# OnOnfre_DevBoard_rev4.net
KiCad netlist of a schematic drawn in EAGLE
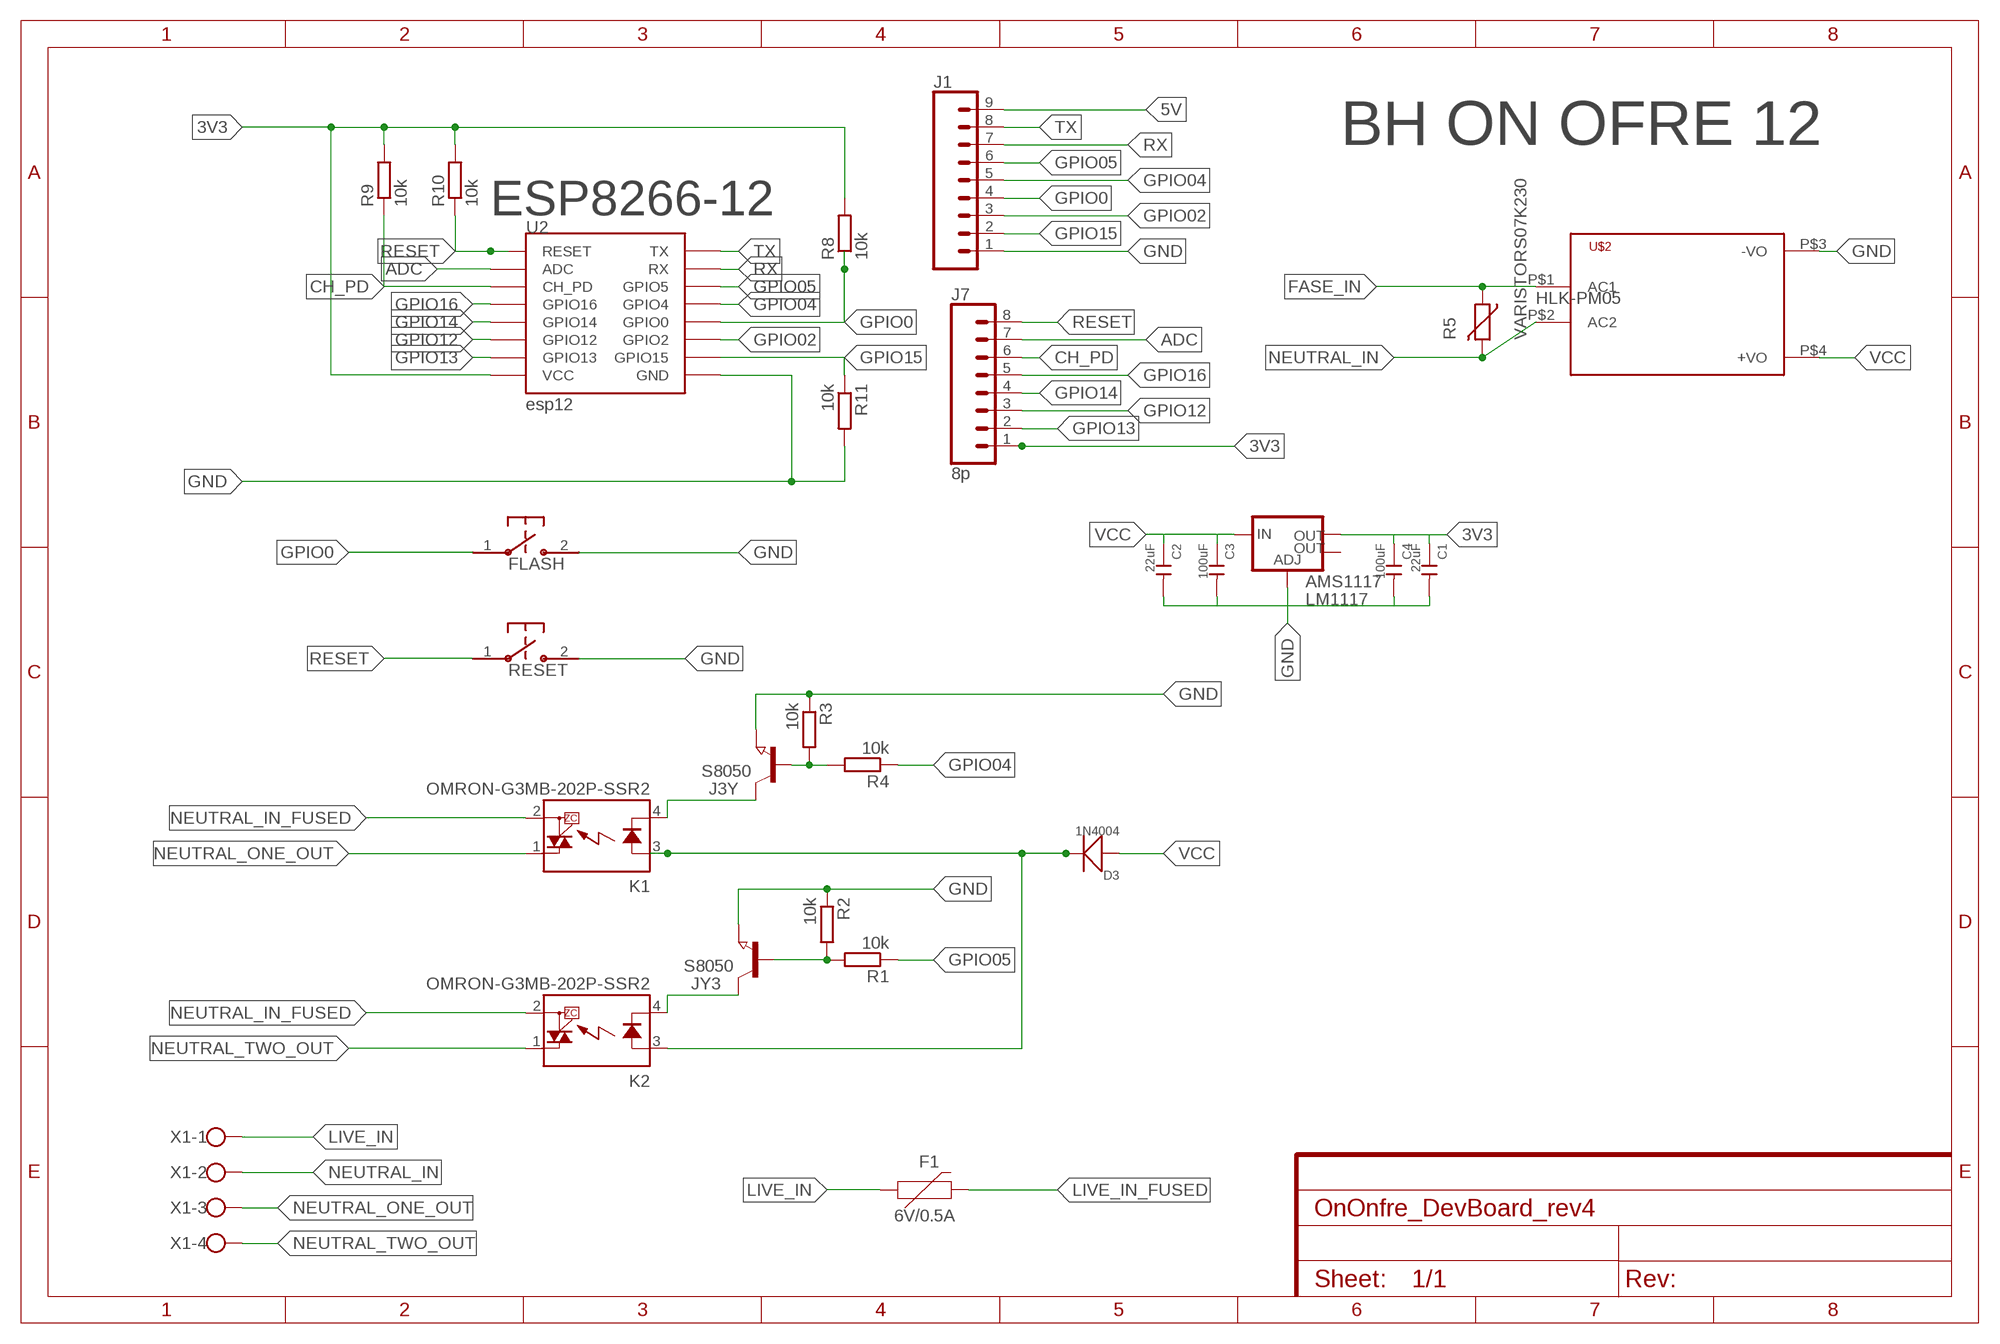
[diagram p0: schematic, sheet 1]

(export (version "E")
  (design (tool "Eeschema 10.0.6"))
  (components
    (comp (ref "AMS1117")
      (value "LM1117")
      (footprint "eagle-import:SOT223")
      (libsource (lib "eagle-import") (part "V_REG_LM1117SOT223"))
    )
    (comp (ref "C1")
      (value "22uF")
      (footprint "eagle-import:C1206")
      (fields (field (name "MPN") "CC1206KKX7RCBB102"))
      (libsource (lib "eagle-import") (part "CERAMIC-1NF-1KV-10%-X7R?(1206)"))
    )
    (comp (ref "C2")
      (value "22uF")
      (footprint "eagle-import:C1206")
      (fields (field (name "MPN") "CC1206KKX7RCBB102"))
      (libsource (lib "eagle-import") (part "CERAMIC-1NF-1KV-10%-X7R?(1206)"))
    )
    (comp (ref "C3")
      (value "100uF")
      (footprint "eagle-import:C1206")
      (fields (field (name "MPN") "CC1206KKX7RCBB102"))
      (libsource (lib "eagle-import") (part "CERAMIC-1NF-1KV-10%-X7R?(1206)"))
    )
    (comp (ref "C4")
      (value "100uF")
      (footprint "eagle-import:C1206")
      (fields (field (name "MPN") "CC1206KKX7RCBB102"))
      (libsource (lib "eagle-import") (part "CERAMIC-1NF-1KV-10%-X7R?(1206)"))
    )
    (comp (ref "D3")
      (value "1N4004")
      (footprint "eagle-import:DO-214AC")
      (fields (field (name "MPN") "1N4007"))
      (libsource (lib "eagle-import") (part "DIODE-GEN-PURPOSE-1KV-1A(DO-214AC)"))
    )
    (comp (ref "F1")
      (value "6V/0.5A")
      (footprint "eagle-import:1206")
      (libsource (lib "eagle-import") (part "PPTC_HALF-AMP"))
    )
    (comp (ref "FLASH")
      (value "B3U-1000P-2P-SMD")
      (footprint "eagle-import:B3U-1000P")
      (fields (field (name "MANUFACTURER") "Omron") (field (name "MPN") "B3U-1000P"))
      (libsource (lib "eagle-import") (part "B3U-1000P"))
    )
    (comp (ref "J1")
      (value "CONN_09")
      (footprint "eagle-import:1X09")
      (libsource (lib "eagle-import") (part "CONN_09"))
    )
    (comp (ref "J3Y")
      (value "S8050")
      (footprint "eagle-import:SOT23")
      (libsource (lib "eagle-import") (part "NPN-TRANSISTOR_SOT23"))
    )
    (comp (ref "J7")
      (value "8p")
      (footprint "eagle-import:1X08")
      (libsource (lib "eagle-import") (part "CONN_08{dblquote}"))
    )
    (comp (ref "JY3")
      (value "S8050")
      (footprint "eagle-import:SOT23")
      (libsource (lib "eagle-import") (part "NPN-TRANSISTOR_SOT23"))
    )
    (comp (ref "K1")
      (value "OMRON-G3MB-202P-SSR2")
      (footprint "eagle-import:OMRON-G3MB-202P-SSR")
      (fields (field (name "MPN") "S202S02F"))
      (libsource (lib "eagle-import") (part "OMRON-G3MB-202P-SSR2"))
    )
    (comp (ref "K2")
      (value "OMRON-G3MB-202P-SSR2")
      (footprint "eagle-import:OMRON-G3MB-202P-SSR")
      (fields (field (name "MPN") "S202S02F"))
      (libsource (lib "eagle-import") (part "OMRON-G3MB-202P-SSR2"))
    )
    (comp (ref "R1")
      (value "10k")
      (footprint "eagle-import:R0603")
      (libsource (lib "eagle-import") (part "R-EU_R0603"))
    )
    (comp (ref "R2")
      (value "10k")
      (footprint "eagle-import:R0603")
      (libsource (lib "eagle-import") (part "R-EU_R0603"))
    )
    (comp (ref "R3")
      (value "10k")
      (footprint "eagle-import:R0603")
      (libsource (lib "eagle-import") (part "R-EU_R0603"))
    )
    (comp (ref "R4")
      (value "10k")
      (footprint "eagle-import:R0603")
      (libsource (lib "eagle-import") (part "R-EU_R0603"))
    )
    (comp (ref "R5")
      (value "VARISTORS07K230")
      (footprint "eagle-import:S07K230")
      (libsource (lib "eagle-import") (part "VARISTORS07K230"))
    )
    (comp (ref "R8")
      (value "10k")
      (footprint "eagle-import:R0603")
      (libsource (lib "eagle-import") (part "R-EU_R0603"))
    )
    (comp (ref "R9")
      (value "10k")
      (footprint "eagle-import:R0603")
      (libsource (lib "eagle-import") (part "R-EU_R0603"))
    )
    (comp (ref "R10")
      (value "10k")
      (footprint "eagle-import:R0603")
      (libsource (lib "eagle-import") (part "R-EU_R0603"))
    )
    (comp (ref "R11")
      (value "10k")
      (footprint "eagle-import:R0603")
      (libsource (lib "eagle-import") (part "R-EU_R0603"))
    )
    (comp (ref "RESET")
      (value "B3U-1000P-2P-SMD")
      (footprint "eagle-import:B3U-1000P")
      (fields (field (name "MANUFACTURER") "Omron") (field (name "MPN") "B3U-1000P"))
      (libsource (lib "eagle-import") (part "B3U-1000P"))
    )
    (comp (ref "U$2")
      (value "HKLPM01")
      (footprint "eagle-import:HKLPM01")
      (libsource (lib "eagle-import") (part "HKLPM01"))
    )
    (comp (ref "U2")
      (value "esp12")
      (footprint "eagle-import:ESP12-SMD")
      (libsource (lib "eagle-import") (part "ESP12SMD"))
    )
    (comp (ref "X1")
      (value "W237-4")
      (footprint "eagle-import:W237-4")
      (libsource (lib "eagle-import") (part "W237-4"))
    )
  )
  (nets
    (net (code "1") (name "3V3") (class "Default")
      (node (ref "AMS1117") (pin "2") (pinfunction "OUT_2") (pintype "output"))
      (node (ref "C1") (pin "1") (pinfunction "1_1") (pintype "passive"))
      (node (ref "C4") (pin "1") (pinfunction "1_1") (pintype "passive"))
      (node (ref "J7") (pin "1") (pinfunction "1_1") (pintype "passive"))
      (node (ref "R10") (pin "2") (pinfunction "2_2") (pintype "passive"))
      (node (ref "R8") (pin "2") (pinfunction "2_2") (pintype "passive"))
      (node (ref "R9") (pin "2") (pinfunction "2_2") (pintype "passive"))
      (node (ref "U2") (pin "VCC") (pinfunction "VCC_VCC") (pintype "bidirectional"))
    )
    (net (code "2") (name "5V") (class "Default")
      (node (ref "D3") (pin "2") (pinfunction "-_2") (pintype "passive"))
      (node (ref "J1") (pin "9") (pinfunction "9_9") (pintype "passive"))
      (node (ref "K1") (pin "3") (pinfunction "A_3") (pintype "passive"))
      (node (ref "K2") (pin "3") (pinfunction "A_3") (pintype "passive"))
    )
    (net (code "3") (name "ADC") (class "Default")
      (node (ref "J7") (pin "7") (pinfunction "7_7") (pintype "passive"))
      (node (ref "U2") (pin "ADC") (pinfunction "ADC_ADC") (pintype "bidirectional"))
    )
    (net (code "4") (name "CH_PD") (class "Default")
      (node (ref "J7") (pin "6") (pinfunction "6_6") (pintype "passive"))
      (node (ref "R9") (pin "1") (pinfunction "1_1") (pintype "passive"))
      (node (ref "U2") (pin "CH_PD") (pinfunction "CH_PD_CH_PD") (pintype "bidirectional"))
    )
    (net (code "5") (name "FASE_IN") (class "Default")
      (node (ref "R5") (pin "1") (pinfunction "1_1") (pintype "passive"))
      (node (ref "U$2") (pin "P$1") (pinfunction "AC1_P$1") (pintype "bidirectional"))
    )
    (net (code "6") (name "GND") (class "Default")
      (node (ref "AMS1117") (pin "1") (pinfunction "ADJ_1") (pintype "input"))
      (node (ref "C1") (pin "2") (pinfunction "2_2") (pintype "passive"))
      (node (ref "C2") (pin "2") (pinfunction "2_2") (pintype "passive"))
      (node (ref "C3") (pin "2") (pinfunction "2_2") (pintype "passive"))
      (node (ref "C4") (pin "2") (pinfunction "2_2") (pintype "passive"))
      (node (ref "FLASH") (pin "2") (pinfunction "P$2_2") (pintype "passive"))
      (node (ref "J1") (pin "1") (pinfunction "1_1") (pintype "passive"))
      (node (ref "J3Y") (pin "2") (pinfunction "E_2") (pintype "passive"))
      (node (ref "JY3") (pin "2") (pinfunction "E_2") (pintype "passive"))
      (node (ref "R11") (pin "2") (pinfunction "2_2") (pintype "passive"))
      (node (ref "R2") (pin "1") (pinfunction "1_1") (pintype "passive"))
      (node (ref "R3") (pin "1") (pinfunction "1_1") (pintype "passive"))
      (node (ref "RESET") (pin "2") (pinfunction "P$2_2") (pintype "passive"))
      (node (ref "U$2") (pin "P$3") (pinfunction "-VO_P$3") (pintype "bidirectional"))
      (node (ref "U2") (pin "GND") (pinfunction "GND_GND") (pintype "bidirectional"))
    )
    (net (code "7") (name "GPIO0") (class "Default")
      (node (ref "FLASH") (pin "1") (pinfunction "P$1_1") (pintype "passive"))
      (node (ref "J1") (pin "4") (pinfunction "4_4") (pintype "passive"))
      (node (ref "R8") (pin "1") (pinfunction "1_1") (pintype "passive"))
      (node (ref "U2") (pin "GPIO0") (pinfunction "GPIO0_GPIO0") (pintype "bidirectional"))
    )
    (net (code "8") (name "GPIO02") (class "Default")
      (node (ref "J1") (pin "3") (pinfunction "3_3") (pintype "passive"))
      (node (ref "U2") (pin "GPIO2") (pinfunction "GPIO2_GPIO2") (pintype "bidirectional"))
    )
    (net (code "9") (name "GPIO04") (class "Default")
      (node (ref "J1") (pin "5") (pinfunction "5_5") (pintype "passive"))
      (node (ref "R4") (pin "1") (pinfunction "1_1") (pintype "passive"))
      (node (ref "U2") (pin "GPIO4") (pinfunction "GPIO4_GPIO4") (pintype "bidirectional"))
    )
    (net (code "10") (name "GPIO05") (class "Default")
      (node (ref "J1") (pin "6") (pinfunction "6_6") (pintype "passive"))
      (node (ref "R1") (pin "1") (pinfunction "1_1") (pintype "passive"))
      (node (ref "U2") (pin "GPIO5") (pinfunction "GPIO5_GPIO5") (pintype "bidirectional"))
    )
    (net (code "11") (name "GPIO12") (class "Default")
      (node (ref "J7") (pin "3") (pinfunction "3_3") (pintype "passive"))
      (node (ref "U2") (pin "GPIO12") (pinfunction "GPIO12_GPIO12") (pintype "bidirectional"))
    )
    (net (code "12") (name "GPIO13") (class "Default")
      (node (ref "J7") (pin "2") (pinfunction "2_2") (pintype "passive"))
      (node (ref "U2") (pin "GPIO13") (pinfunction "GPIO13_GPIO13") (pintype "bidirectional"))
    )
    (net (code "13") (name "GPIO14") (class "Default")
      (node (ref "J7") (pin "4") (pinfunction "4_4") (pintype "passive"))
      (node (ref "U2") (pin "GPIO14") (pinfunction "GPIO14_GPIO14") (pintype "bidirectional"))
    )
    (net (code "14") (name "GPIO15") (class "Default")
      (node (ref "J1") (pin "2") (pinfunction "2_2") (pintype "passive"))
      (node (ref "R11") (pin "1") (pinfunction "1_1") (pintype "passive"))
      (node (ref "U2") (pin "GPIO15") (pinfunction "GPIO15_GPIO15") (pintype "bidirectional"))
    )
    (net (code "15") (name "GPIO16") (class "Default")
      (node (ref "J7") (pin "5") (pinfunction "5_5") (pintype "passive"))
      (node (ref "U2") (pin "GPIO16") (pinfunction "GPIO16_GPIO16") (pintype "bidirectional"))
    )
    (net (code "16") (name "LIVE_IN") (class "Default")
      (node (ref "F1") (pin "1") (pinfunction "1_1") (pintype "bidirectional"))
      (node (ref "X1") (pin "1") (pinfunction "KL_1") (pintype "passive"))
    )
    (net (code "17") (name "LIVE_IN_FUSED") (class "Default")
      (node (ref "F1") (pin "2") (pinfunction "2_2") (pintype "bidirectional"))
    )
    (net (code "18") (name "NEUTRAL_IN") (class "Default")
      (node (ref "R5") (pin "2") (pinfunction "2_2") (pintype "passive"))
      (node (ref "U$2") (pin "P$2") (pinfunction "AC2_P$2") (pintype "bidirectional"))
      (node (ref "X1") (pin "2") (pinfunction "KL_2") (pintype "passive"))
    )
    (net (code "19") (name "NEUTRAL_IN_FUSED") (class "Default")
      (node (ref "K1") (pin "2") (pinfunction "DS2_2") (pintype "passive"))
      (node (ref "K2") (pin "2") (pinfunction "DS2_2") (pintype "passive"))
    )
    (net (code "20") (name "NEUTRAL_ONE_OUT") (class "Default")
      (node (ref "K1") (pin "1") (pinfunction "DS1_1") (pintype "passive"))
      (node (ref "X1") (pin "3") (pinfunction "KL_3") (pintype "passive"))
    )
    (net (code "21") (name "NEUTRAL_TWO_OUT") (class "Default")
      (node (ref "K2") (pin "1") (pinfunction "DS1_1") (pintype "passive"))
      (node (ref "X1") (pin "4") (pinfunction "KL_4") (pintype "passive"))
    )
    (net (code "22") (name "Net-(J3Y-B)") (class "Default")
      (node (ref "J3Y") (pin "1") (pinfunction "B_1") (pintype "passive"))
      (node (ref "R3") (pin "2") (pinfunction "2_2") (pintype "passive"))
      (node (ref "R4") (pin "2") (pinfunction "2_2") (pintype "passive"))
    )
    (net (code "23") (name "Net-(J3Y-C)") (class "Default")
      (node (ref "J3Y") (pin "3") (pinfunction "C_3") (pintype "passive"))
      (node (ref "K1") (pin "4") (pinfunction "K_4") (pintype "passive"))
    )
    (net (code "24") (name "Net-(JY3-B)") (class "Default")
      (node (ref "JY3") (pin "1") (pinfunction "B_1") (pintype "passive"))
      (node (ref "R1") (pin "2") (pinfunction "2_2") (pintype "passive"))
      (node (ref "R2") (pin "2") (pinfunction "2_2") (pintype "passive"))
    )
    (net (code "25") (name "Net-(JY3-C)") (class "Default")
      (node (ref "JY3") (pin "3") (pinfunction "C_3") (pintype "passive"))
      (node (ref "K2") (pin "4") (pinfunction "K_4") (pintype "passive"))
    )
    (net (code "26") (name "RESET") (class "Default")
      (node (ref "J7") (pin "8") (pinfunction "8_8") (pintype "passive"))
      (node (ref "R10") (pin "1") (pinfunction "1_1") (pintype "passive"))
      (node (ref "RESET") (pin "1") (pinfunction "P$1_1") (pintype "passive"))
      (node (ref "U2") (pin "RESET") (pinfunction "RESET_RESET") (pintype "bidirectional"))
    )
    (net (code "27") (name "RX") (class "Default")
      (node (ref "J1") (pin "7") (pinfunction "7_7") (pintype "passive"))
      (node (ref "U2") (pin "RXD0") (pinfunction "RX_RXD0") (pintype "bidirectional"))
    )
    (net (code "28") (name "TX") (class "Default")
      (node (ref "J1") (pin "8") (pinfunction "8_8") (pintype "passive"))
      (node (ref "U2") (pin "TXD0") (pinfunction "TX_TXD0") (pintype "bidirectional"))
    )
    (net (code "29") (name "VCC") (class "Default")
      (node (ref "AMS1117") (pin "3") (pinfunction "IN_3") (pintype "input"))
      (node (ref "C2") (pin "1") (pinfunction "1_1") (pintype "passive"))
      (node (ref "C3") (pin "1") (pinfunction "1_1") (pintype "passive"))
      (node (ref "D3") (pin "1") (pinfunction "+_1") (pintype "passive"))
      (node (ref "U$2") (pin "P$4") (pinfunction "+VO_P$4") (pintype "bidirectional"))
    )
    (net (code "30") (name "unconnected-(AMS1117-OUT-Pad4)") (class "Default")
      (node (ref "AMS1117") (pin "4") (pinfunction "OUT_4") (pintype "output"))
    )
  )
)
